# h_bridge_schdc.net
KiCad netlist of a schematic drawn in Altium Designer
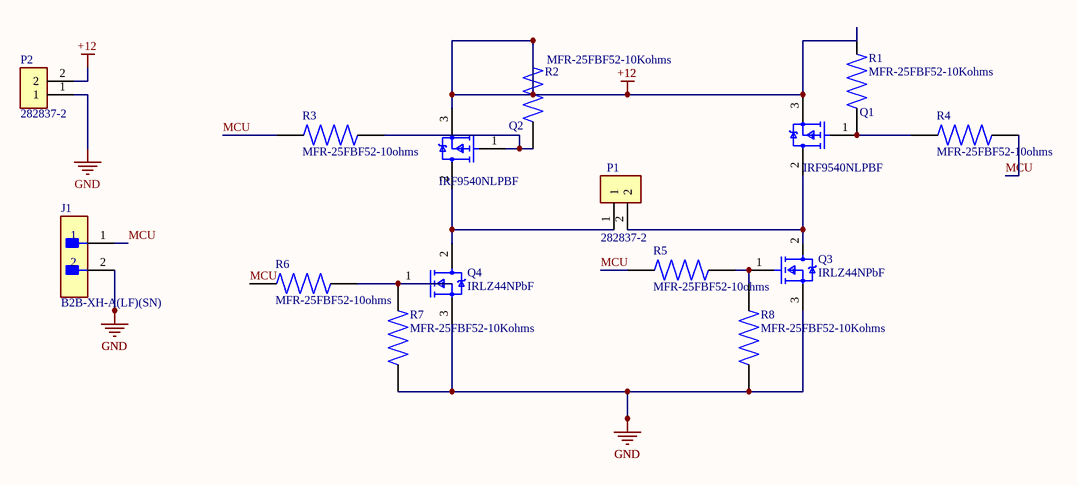
[diagram p0: h bridge.schdc.SchDoc]

(export (version "E")
  (design (tool "Eeschema 10.0.6"))
  (components
    (comp (ref "J1")
      (value "B2B-XH-A(LF)(SN)")
      (footprint "FP-B2B-XH-A_LF_SN-MFG")
      (description "CONN HEADER VERT 2POS 2.5MM")
      (libsource (lib "Altium Content Vault") (part "3bc925449376181038e59eaffc5286c"))
    )
    (comp (ref "P1")
      (value "282837-2")
      (footprint "TE_282837-2")
      (description "12v .3A")
      (fields (field (name "MF") "TE Connectivity"))
      (libsource (lib "282837-2") (part "282837-2"))
    )
    (comp (ref "P2")
      (value "282837-2")
      (footprint "TE_282837-2")
      (fields (field (name "MF") "TE Connectivity"))
      (libsource (lib "") (part "282837-2_1"))
    )
    (comp (ref "Q1")
      (value "IRF9540NLPBF")
      (footprint "FP-PG-TO262-3-MFG")
      (description "MOSFET P-CH 100V 23A TO262-3")
      (libsource (lib "Altium Content Vault") (part "38cbee71a1bce1ebb3b8a3a9639eda0"))
    )
    (comp (ref "Q2")
      (value "IRF9540NLPBF")
      (footprint "FP-PG-TO262-3-MFG")
      (description "MOSFET P-CH 100V 23A TO262-3")
      (libsource (lib "Altium Content Vault") (part "38cbee71a1bce1ebb3b8a3a9639eda0"))
    )
    (comp (ref "Q3")
      (value "IRLZ44NPbF")
      (footprint "FP-PG-TO220-3-MFG")
      (description "MOSFET N-CH 55V 47A TO220AB")
      (libsource (lib "Altium Content Vault") (part "b09f7f152735e370c1ea22a33fa83d6"))
    )
    (comp (ref "Q4")
      (value "IRLZ44NPbF")
      (footprint "FP-PG-TO220-3-MFG")
      (description "MOSFET N-CH 55V 47A TO220AB")
      (libsource (lib "Altium Content Vault") (part "b09f7f152735e370c1ea22a33fa83d6"))
    )
    (comp (ref "R1")
      (value "MFR-25FBF52-10Kohms")
      (footprint "RESAD1100W55L680D260")
      (description "10K Ohms Â±1% 0.25W, 1/4W Through Hole Resistor Axial - Metal Film")
      (fields (field (name "MF") "Yageo") (field (name "MP") "MFR-25FBF52-1K"))
      (libsource (lib "MFR-25FBF52-1K") (part "MFR-25FBF52-1K"))
    )
    (comp (ref "R2")
      (value "MFR-25FBF52-10Kohms")
      (footprint "RESAD1100W55L680D260")
      (description "10K Ohms Â±1% 0.25W, 1/4W Through Hole Resistor Axial - Metal Film")
      (fields (field (name "MF") "Yageo") (field (name "MP") "MFR-25FBF52-1K"))
      (libsource (lib "MFR-25FBF52-1K") (part "MFR-25FBF52-1K"))
    )
    (comp (ref "R3")
      (value "MFR-25FBF52-10ohms")
      (footprint "RESAD1100W55L680D260")
      (description "10 Ohms Â±1% 0.25W, 1/4W Through Hole Resistor Axial - Metal Film")
      (fields (field (name "MF") "Yageo") (field (name "MP") "MFR-25FBF52-1K"))
      (libsource (lib "MFR-25FBF52-1K") (part "MFR-25FBF52-1K"))
    )
    (comp (ref "R4")
      (value "MFR-25FBF52-10ohms")
      (footprint "RESAD1100W55L680D260")
      (description "10 Ohms Â±1% 0.25W, 1/4W Through Hole Resistor Axial - Metal Film")
      (fields (field (name "MF") "Yageo") (field (name "MP") "MFR-25FBF52-1K"))
      (libsource (lib "MFR-25FBF52-1K") (part "MFR-25FBF52-1K"))
    )
    (comp (ref "R5")
      (value "MFR-25FBF52-10ohms")
      (footprint "RESAD1100W55L680D260")
      (description "10 Ohms Â±1% 0.25W, 1/4W Through Hole Resistor Axial - Metal Film")
      (fields (field (name "MF") "Yageo") (field (name "MP") "MFR-25FBF52-1K"))
      (libsource (lib "MFR-25FBF52-1K") (part "MFR-25FBF52-1K"))
    )
    (comp (ref "R6")
      (value "MFR-25FBF52-10ohms")
      (footprint "RESAD1100W55L680D260")
      (description "10 Ohms Â±1% 0.25W, 1/4W Through Hole Resistor Axial - Metal Film")
      (fields (field (name "MF") "Yageo") (field (name "MP") "MFR-25FBF52-1K"))
      (libsource (lib "MFR-25FBF52-1K") (part "MFR-25FBF52-1K"))
    )
    (comp (ref "R7")
      (value "MFR-25FBF52-10Kohms")
      (footprint "RESAD1100W55L680D260")
      (description "10K Ohms Â±1% 0.25W, 1/4W Through Hole Resistor Axial - Metal Film")
      (fields (field (name "MF") "Yageo") (field (name "MP") "MFR-25FBF52-1K"))
      (libsource (lib "MFR-25FBF52-1K") (part "MFR-25FBF52-1K"))
    )
    (comp (ref "R8")
      (value "MFR-25FBF52-10Kohms")
      (footprint "RESAD1100W55L680D260")
      (description "10K Ohms Â±1% 0.25W, 1/4W Through Hole Resistor Axial - Metal Film")
      (fields (field (name "MF") "Yageo") (field (name "MP") "MFR-25FBF52-1K"))
      (libsource (lib "MFR-25FBF52-1K") (part "MFR-25FBF52-1K"))
    )
  )
  (nets
    (net (code "1") (name "+12") (class "Default")
      (node (ref "P2") (pin "2") (pinfunction "2_2") (pintype "passive"))
      (node (ref "Q1") (pin "3") (pinfunction "Source_3") (pintype "passive"))
      (node (ref "Q2") (pin "3") (pinfunction "Source_3") (pintype "passive"))
      (node (ref "R1") (pin "2") (pinfunction "2_2") (pintype "passive"))
      (node (ref "R2") (pin "2") (pinfunction "2_2") (pintype "passive"))
    )
    (net (code "2") (name "/MCU") (class "Default")
      (node (ref "J1") (pin "1") (pinfunction "1_1") (pintype "passive"))
      (node (ref "R3") (pin "1") (pinfunction "1_1") (pintype "passive"))
      (node (ref "R4") (pin "1") (pinfunction "1_1") (pintype "passive"))
      (node (ref "R5") (pin "2") (pinfunction "2_2") (pintype "passive"))
      (node (ref "R6") (pin "1") (pinfunction "1_1") (pintype "passive"))
    )
    (net (code "3") (name "GND") (class "Default")
      (node (ref "J1") (pin "2") (pinfunction "2_2") (pintype "passive"))
      (node (ref "P2") (pin "1") (pinfunction "1_1") (pintype "passive"))
      (node (ref "Q3") (pin "3") (pinfunction "S_3") (pintype "passive"))
      (node (ref "Q4") (pin "3") (pinfunction "S_3") (pintype "passive"))
      (node (ref "R7") (pin "1") (pinfunction "1_1") (pintype "passive"))
      (node (ref "R8") (pin "1") (pinfunction "1_1") (pintype "passive"))
    )
    (net (code "4") (name "Net-(Q1-Drain)") (class "Default")
      (node (ref "P1") (pin "2") (pinfunction "2_2") (pintype "passive"))
      (node (ref "Q1") (pin "2") (pinfunction "Drain_2") (pintype "passive"))
      (node (ref "Q3") (pin "2") (pinfunction "D_2") (pintype "passive"))
    )
    (net (code "5") (name "Net-(Q1-Gate)") (class "Default")
      (node (ref "Q1") (pin "1") (pinfunction "Gate_1") (pintype "passive"))
      (node (ref "R1") (pin "1") (pinfunction "1_1") (pintype "passive"))
      (node (ref "R4") (pin "2") (pinfunction "2_2") (pintype "passive"))
    )
    (net (code "6") (name "Net-(Q2-Drain)") (class "Default")
      (node (ref "P1") (pin "1") (pinfunction "1_1") (pintype "passive"))
      (node (ref "Q2") (pin "2") (pinfunction "Drain_2") (pintype "passive"))
      (node (ref "Q4") (pin "2") (pinfunction "D_2") (pintype "passive"))
    )
    (net (code "7") (name "Net-(Q2-Gate)") (class "Default")
      (node (ref "Q2") (pin "1") (pinfunction "Gate_1") (pintype "passive"))
      (node (ref "R2") (pin "1") (pinfunction "1_1") (pintype "passive"))
      (node (ref "R3") (pin "2") (pinfunction "2_2") (pintype "passive"))
    )
    (net (code "8") (name "Net-(Q3-G)") (class "Default")
      (node (ref "Q3") (pin "1") (pinfunction "G_1") (pintype "passive"))
      (node (ref "R5") (pin "1") (pinfunction "1_1") (pintype "passive"))
      (node (ref "R8") (pin "2") (pinfunction "2_2") (pintype "passive"))
    )
    (net (code "9") (name "Net-(Q4-G)") (class "Default")
      (node (ref "Q4") (pin "1") (pinfunction "G_1") (pintype "passive"))
      (node (ref "R6") (pin "2") (pinfunction "2_2") (pintype "passive"))
      (node (ref "R7") (pin "2") (pinfunction "2_2") (pintype "passive"))
    )
  )
)
